# lab1_chernov_usb_i2c.net
KiCad netlist of a schematic drawn in Altium Designer
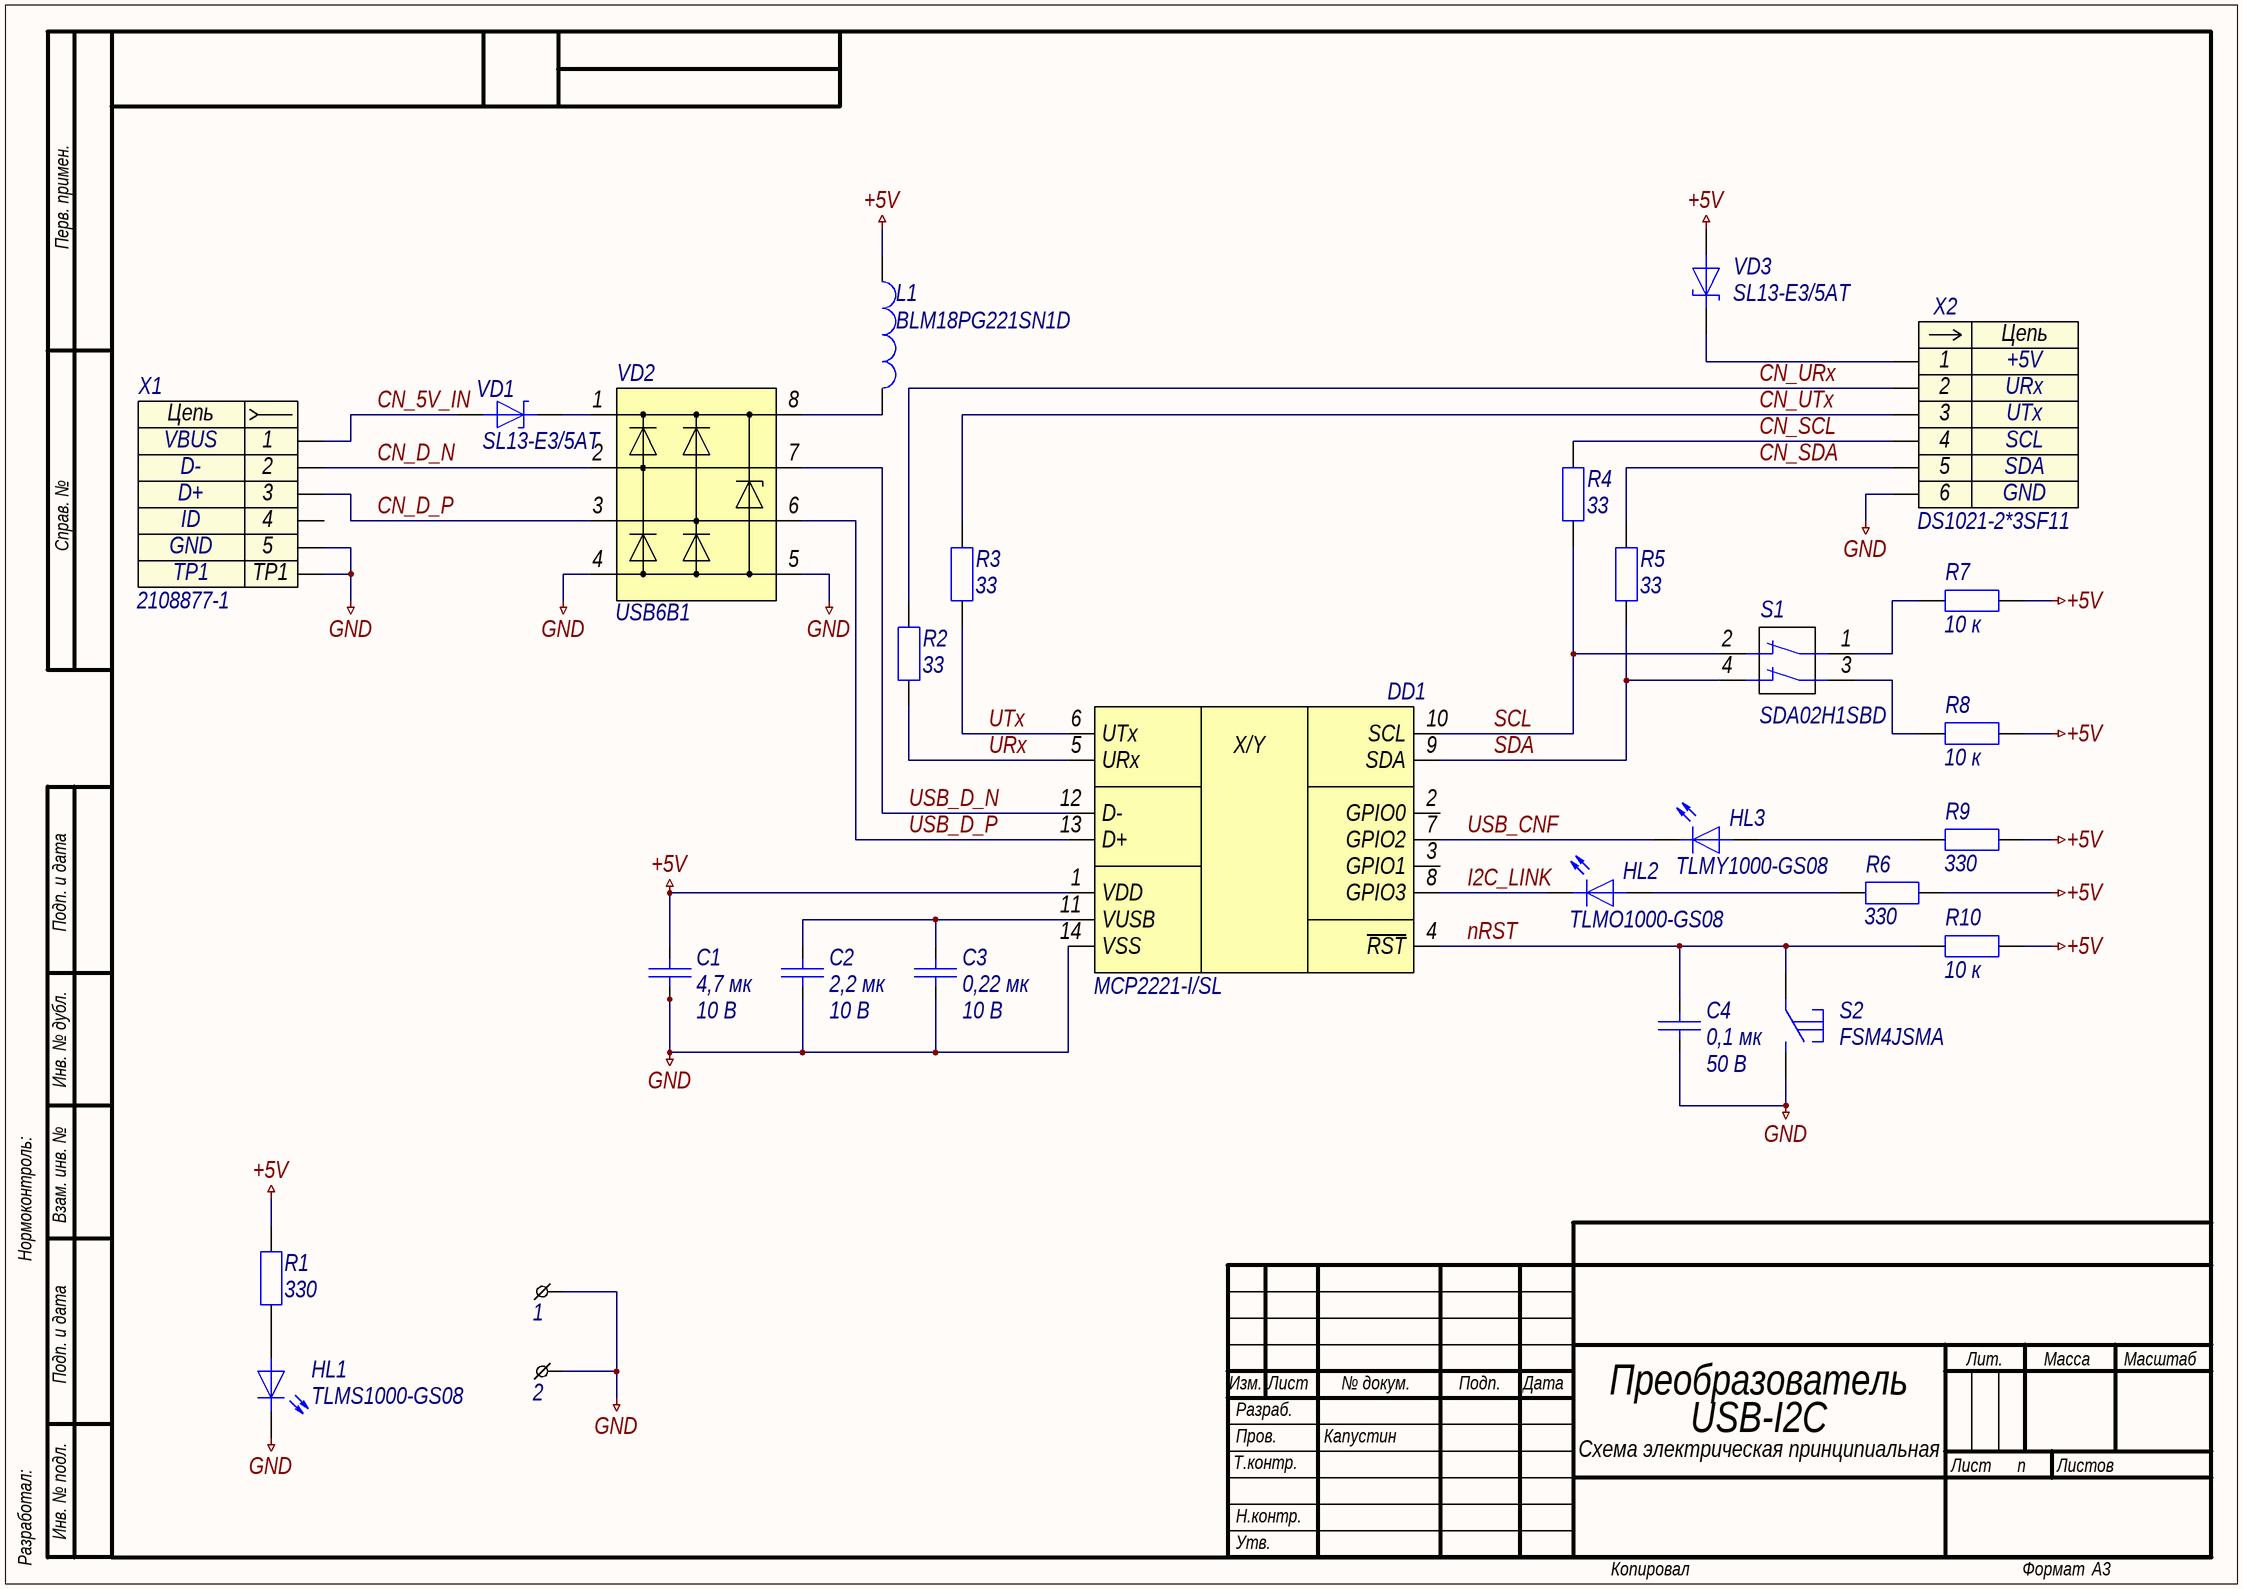
[diagram p0: lab1_chernov_usb_i2c.SchDoc]

(export (version "E")
  (design (tool "Eeschema 10.0.6"))
  (components
    (comp (ref "1")
      (value "MOUNTING_HOLE")
      (footprint "Lib:HOLE_1,6X3,3")
      (libsource (lib "Lib") (part "Отверстие 1,6x3,3"))
    )
    (comp (ref "2")
      (value "MOUNTING_HOLE")
      (footprint "Lib:HOLE_1,6X3,3")
      (libsource (lib "Lib") (part "Отверстие 1,6x3,3"))
    )
    (comp (ref "C1")
      (value "4,7 мк")
      (footprint "C0603")
      (description "=Описание")
      (fields (field (name "НАПРЯЖЕНИЕ") "10 В"))
      (libsource (lib "Database_Students") (part "C-NONPOLAR"))
    )
    (comp (ref "C2")
      (value "2,2 мк")
      (footprint "C0603")
      (description "=Описание")
      (fields (field (name "НАПРЯЖЕНИЕ") "10 В"))
      (libsource (lib "Database_Students") (part "C-NONPOLAR"))
    )
    (comp (ref "C3")
      (value "0,22 мк")
      (footprint "C0603")
      (description "=Описание")
      (fields (field (name "НАПРЯЖЕНИЕ") "10 В"))
      (libsource (lib "Database_Students") (part "C-NONPOLAR"))
    )
    (comp (ref "C4")
      (value "0,1 мк")
      (footprint "C0603")
      (description "=Описание")
      (fields (field (name "НАПРЯЖЕНИЕ") "50 В"))
      (libsource (lib "Database_Students") (part "C-NONPOLAR"))
    )
    (comp (ref "DD1")
      (value "MCP2221-I/SL")
      (footprint "mcp2221:SOIC127P600X175-14N")
      (libsource (lib "mcp2221") (part "MCP2221-I/SL"))
    )
    (comp (ref "HL1")
      (value "TLMS1000-GS08")
      (footprint "HL0603")
      (description "=Описание")
      (libsource (lib "Database_Students") (part "HL-COMMON"))
    )
    (comp (ref "HL2")
      (value "TLMO1000-GS08")
      (footprint "HL0603")
      (description "=Описание")
      (libsource (lib "Database_Students") (part "HL-COMMON"))
    )
    (comp (ref "HL3")
      (value "TLMY1000-GS08")
      (footprint "HL0603")
      (description "=Описание")
      (libsource (lib "Database_Students") (part "HL-COMMON"))
    )
    (comp (ref "L1")
      (value "BLM18PG221SN1D")
      (footprint "BLM-2-0603")
      (description "=Описание")
      (libsource (lib "Database_Students") (part "FERRITE-BEAD"))
    )
    (comp (ref "R1")
      (value "330")
      (footprint "R0603")
      (description "=Описание")
      (libsource (lib "Database_Students") (part "R-COMMON"))
    )
    (comp (ref "R2")
      (value "33")
      (footprint "R0603")
      (description "=Описание")
      (libsource (lib "Database_Students") (part "R-COMMON"))
    )
    (comp (ref "R3")
      (value "33")
      (footprint "R0603")
      (description "=Описание")
      (libsource (lib "Database_Students") (part "R-COMMON"))
    )
    (comp (ref "R4")
      (value "33")
      (footprint "R0603")
      (description "=Описание")
      (libsource (lib "Database_Students") (part "R-COMMON"))
    )
    (comp (ref "R5")
      (value "33")
      (footprint "R0603")
      (description "=Описание")
      (libsource (lib "Database_Students") (part "R-COMMON"))
    )
    (comp (ref "R6")
      (value "330")
      (footprint "R0603")
      (description "=Описание")
      (libsource (lib "Database_Students") (part "R-COMMON"))
    )
    (comp (ref "R7")
      (value "10 к")
      (footprint "R0603")
      (description "=Описание")
      (libsource (lib "Database_Students") (part "R-COMMON"))
    )
    (comp (ref "R8")
      (value "10 к")
      (footprint "R0603")
      (description "=Описание")
      (libsource (lib "Database_Students") (part "R-COMMON"))
    )
    (comp (ref "R9")
      (value "330")
      (footprint "R0603")
      (description "=Описание")
      (libsource (lib "Database_Students") (part "R-COMMON"))
    )
    (comp (ref "R10")
      (value "10 к")
      (footprint "R0603")
      (description "=Описание")
      (libsource (lib "Database_Students") (part "R-COMMON"))
    )
    (comp (ref "S1")
      (value "SDA02H1SBD")
      (footprint "DIP-SWITCH-02-706X930X545")
      (description "=Описание")
      (libsource (lib "Database_Students") (part "SWITCH-02"))
    )
    (comp (ref "S2")
      (value "FSM4JSMA")
      (footprint "FSM4JSMA")
      (description "=Описание")
      (libsource (lib "Database_Students") (part "SWITCH-01"))
    )
    (comp (ref "VD1")
      (value "SL13-E3/5AT")
      (footprint "DO-214AC")
      (description "=Описание")
      (libsource (lib "Database_Students") (part "DIODE-SCHOTTKY"))
    )
    (comp (ref "VD2")
      (value "USB6B1")
      (footprint "SO-8")
      (description "=Описание")
      (libsource (lib "Database_Students") (part "USB6B1"))
    )
    (comp (ref "VD3")
      (value "SL13-E3/5AT")
      (footprint "DO-214AC")
      (description "=Описание")
      (libsource (lib "Database_Students") (part "DIODE-SCHOTTKY"))
    )
    (comp (ref "X1")
      (value "2108877-1")
      (footprint "2108877-1")
      (description "=Описание")
      (libsource (lib "Database_Students") (part "HEADER-5-TP1-SCT"))
    )
    (comp (ref "X2")
      (value "DS1021-2*3SF11")
      (footprint "DS1021-2X3SF11")
      (description "=Описание")
      (libsource (lib "Database_Students") (part "HEADER-6-PLG"))
    )
  )
  (nets
    (net (code "1") (name "+5V") (class "Default")
      (node (ref "C1") (pin "2") (pinfunction "2_2") (pintype "passive"))
      (node (ref "DD1") (pin "1") (pinfunction "VDD_1") (pintype "passive"))
      (node (ref "L1") (pin "1") (pinfunction "1_1") (pintype "passive"))
      (node (ref "R1") (pin "1") (pinfunction "1_1") (pintype "passive"))
      (node (ref "R10") (pin "2") (pinfunction "2_2") (pintype "passive"))
      (node (ref "R6") (pin "2") (pinfunction "2_2") (pintype "passive"))
      (node (ref "R7") (pin "2") (pinfunction "2_2") (pintype "passive"))
      (node (ref "R8") (pin "2") (pinfunction "2_2") (pintype "passive"))
      (node (ref "R9") (pin "2") (pinfunction "2_2") (pintype "passive"))
      (node (ref "VD3") (pin "2") (pinfunction "2_2") (pintype "passive"))
    )
    (net (code "2") (name "/CN_5V_IN") (class "Default")
      (node (ref "VD1") (pin "2") (pinfunction "2_2") (pintype "passive"))
      (node (ref "X1") (pin "1") (pinfunction "1_1") (pintype "passive"))
    )
    (net (code "3") (name "/CN_D_N") (class "Default")
      (node (ref "VD2") (pin "2") (pinfunction "2_2") (pintype "passive"))
      (node (ref "X1") (pin "2") (pinfunction "2_2") (pintype "passive"))
    )
    (net (code "4") (name "/CN_D_P") (class "Default")
      (node (ref "VD2") (pin "3") (pinfunction "3_3") (pintype "passive"))
      (node (ref "X1") (pin "3") (pinfunction "3_3") (pintype "passive"))
    )
    (net (code "5") (name "/CN_SCL") (class "Default")
      (node (ref "R4") (pin "1") (pinfunction "1_1") (pintype "passive"))
      (node (ref "X2") (pin "4") (pinfunction "4_4") (pintype "passive"))
    )
    (net (code "6") (name "/CN_SDA") (class "Default")
      (node (ref "R5") (pin "1") (pinfunction "1_1") (pintype "passive"))
      (node (ref "X2") (pin "5") (pinfunction "5_5") (pintype "passive"))
    )
    (net (code "7") (name "/CN_URx") (class "Default")
      (node (ref "R2") (pin "1") (pinfunction "1_1") (pintype "passive"))
      (node (ref "X2") (pin "2") (pinfunction "2_2") (pintype "passive"))
    )
    (net (code "8") (name "/CN_UTx") (class "Default")
      (node (ref "R3") (pin "1") (pinfunction "1_1") (pintype "passive"))
      (node (ref "X2") (pin "3") (pinfunction "3_3") (pintype "passive"))
    )
    (net (code "9") (name "/I2C_LINK") (class "Default")
      (node (ref "DD1") (pin "8") (pinfunction "GPIO3_8") (pintype "passive"))
      (node (ref "HL2") (pin "1") (pinfunction "1_1") (pintype "passive"))
    )
    (net (code "10") (name "/SCL") (class "Default")
      (node (ref "DD1") (pin "10") (pinfunction "SCL_10") (pintype "passive"))
      (node (ref "R4") (pin "2") (pinfunction "2_2") (pintype "passive"))
      (node (ref "S1") (pin "2") (pinfunction "2_2") (pintype "passive"))
    )
    (net (code "11") (name "/SDA") (class "Default")
      (node (ref "DD1") (pin "9") (pinfunction "SDA_9") (pintype "passive"))
      (node (ref "R5") (pin "2") (pinfunction "2_2") (pintype "passive"))
      (node (ref "S1") (pin "4") (pinfunction "4_4") (pintype "passive"))
    )
    (net (code "12") (name "/URx") (class "Default")
      (node (ref "DD1") (pin "5") (pinfunction "URx_5") (pintype "passive"))
      (node (ref "R2") (pin "2") (pinfunction "2_2") (pintype "passive"))
    )
    (net (code "13") (name "/USB_CNF") (class "Default")
      (node (ref "DD1") (pin "7") (pinfunction "GPIO2_7") (pintype "passive"))
      (node (ref "HL3") (pin "1") (pinfunction "1_1") (pintype "passive"))
    )
    (net (code "14") (name "/USB_D_N") (class "Default")
      (node (ref "DD1") (pin "12") (pinfunction "D-_12") (pintype "passive"))
      (node (ref "VD2") (pin "7") (pinfunction "7_7") (pintype "passive"))
    )
    (net (code "15") (name "/USB_D_P") (class "Default")
      (node (ref "DD1") (pin "13") (pinfunction "D+_13") (pintype "passive"))
      (node (ref "VD2") (pin "6") (pinfunction "6_6") (pintype "passive"))
    )
    (net (code "16") (name "/UTx") (class "Default")
      (node (ref "DD1") (pin "6") (pinfunction "UTx_6") (pintype "passive"))
      (node (ref "R3") (pin "2") (pinfunction "2_2") (pintype "passive"))
    )
    (net (code "17") (name "/nRST") (class "Default")
      (node (ref "C4") (pin "2") (pinfunction "2_2") (pintype "passive"))
      (node (ref "DD1") (pin "4") (pinfunction "~{RST}_4") (pintype "passive"))
      (node (ref "R10") (pin "1") (pinfunction "1_1") (pintype "passive"))
      (node (ref "S2") (pin "1") (pinfunction "1_1") (pintype "passive"))
    )
    (net (code "18") (name "GND") (class "Default")
      (node (ref "1") (pin "1") (pinfunction "1_1") (pintype "passive"))
      (node (ref "2") (pin "1") (pinfunction "1_1") (pintype "passive"))
      (node (ref "C1") (pin "1") (pinfunction "1_1") (pintype "passive"))
      (node (ref "C2") (pin "1") (pinfunction "1_1") (pintype "passive"))
      (node (ref "C3") (pin "1") (pinfunction "1_1") (pintype "passive"))
      (node (ref "C4") (pin "1") (pinfunction "1_1") (pintype "passive"))
      (node (ref "DD1") (pin "14") (pinfunction "VSS_14") (pintype "passive"))
      (node (ref "HL1") (pin "1") (pinfunction "1_1") (pintype "passive"))
      (node (ref "S2") (pin "2") (pinfunction "2_2") (pintype "passive"))
      (node (ref "VD2") (pin "4") (pinfunction "4_4") (pintype "passive"))
      (node (ref "VD2") (pin "5") (pinfunction "5_5") (pintype "passive"))
      (node (ref "X1") (pin "5") (pinfunction "5_5") (pintype "passive"))
      (node (ref "X1") (pin "TP1") (pinfunction "TP1_TP1") (pintype "passive"))
      (node (ref "X2") (pin "6") (pinfunction "6_6") (pintype "passive"))
    )
    (net (code "19") (name "Net-(DD1-VUSB)") (class "Default")
      (node (ref "C2") (pin "2") (pinfunction "2_2") (pintype "passive"))
      (node (ref "C3") (pin "2") (pinfunction "2_2") (pintype "passive"))
      (node (ref "DD1") (pin "11") (pinfunction "VUSB_11") (pintype "passive"))
    )
    (net (code "20") (name "Net-(HL1-Pad2)") (class "Default")
      (node (ref "HL1") (pin "2") (pinfunction "2_2") (pintype "passive"))
      (node (ref "R1") (pin "2") (pinfunction "2_2") (pintype "passive"))
    )
    (net (code "21") (name "Net-(HL2-Pad2)") (class "Default")
      (node (ref "HL2") (pin "2") (pinfunction "2_2") (pintype "passive"))
      (node (ref "R6") (pin "1") (pinfunction "1_1") (pintype "passive"))
    )
    (net (code "22") (name "Net-(HL3-Pad2)") (class "Default")
      (node (ref "HL3") (pin "2") (pinfunction "2_2") (pintype "passive"))
      (node (ref "R9") (pin "1") (pinfunction "1_1") (pintype "passive"))
    )
    (net (code "23") (name "Net-(L1-Pad2)") (class "Default")
      (node (ref "L1") (pin "2") (pinfunction "2_2") (pintype "passive"))
      (node (ref "VD2") (pin "8") (pinfunction "8_8") (pintype "passive"))
    )
    (net (code "24") (name "Net-(R7-Pad1)") (class "Default")
      (node (ref "R7") (pin "1") (pinfunction "1_1") (pintype "passive"))
      (node (ref "S1") (pin "1") (pinfunction "1_1") (pintype "passive"))
    )
    (net (code "25") (name "Net-(R8-Pad1)") (class "Default")
      (node (ref "R8") (pin "1") (pinfunction "1_1") (pintype "passive"))
      (node (ref "S1") (pin "3") (pinfunction "3_3") (pintype "passive"))
    )
    (net (code "26") (name "Net-(VD1-Pad1)") (class "Default")
      (node (ref "VD1") (pin "1") (pinfunction "1_1") (pintype "passive"))
      (node (ref "VD2") (pin "1") (pinfunction "1_1") (pintype "passive"))
    )
    (net (code "27") (name "Net-(VD3-Pad1)") (class "Default")
      (node (ref "VD3") (pin "1") (pinfunction "1_1") (pintype "passive"))
      (node (ref "X2") (pin "1") (pinfunction "1_1") (pintype "passive"))
    )
    (net (code "28") (name "unconnected-(DD1-GPIO0-Pad2)") (class "Default")
      (node (ref "DD1") (pin "2") (pinfunction "GPIO0_2") (pintype "passive"))
    )
    (net (code "29") (name "unconnected-(DD1-GPIO1-Pad3)") (class "Default")
      (node (ref "DD1") (pin "3") (pinfunction "GPIO1_3") (pintype "passive"))
    )
    (net (code "30") (name "unconnected-(X1-Pad4)") (class "Default")
      (node (ref "X1") (pin "4") (pinfunction "4_4") (pintype "passive"))
    )
  )
)
